# Flash_-_S25FL216K0PMFI041.net
KiCad netlist of a schematic drawn in Altium Designer
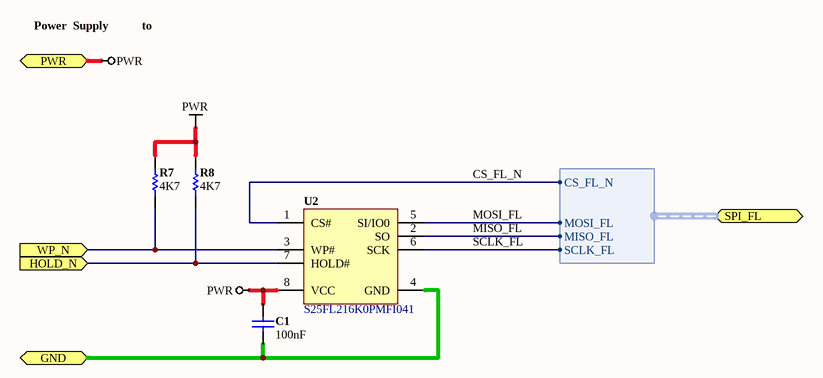
[diagram p0: Flash - S25FL216K0PMFI041.SchDoc]

(export (version "E")
  (design (tool "Eeschema 10.0.6"))
  (components
    (comp (ref "C1")
      (value "100nF")
      (footprint "CAPC0402(1005)60_L")
      (fields
        (field (name "TOLERANCE") "±10%")
        (field (name "MANUFACTURER PART NUMBER") "C0402C104K8PACTU")
        (field (name "Comment") "CAP 100nF 16V 0402(1005)")
      )
      (libsource (lib "Component_Database") (part "CAP_NP"))
    )
    (comp (ref "R7")
      (value "4K7")
      (footprint "RESC0402(1005)40_L")
      (fields
        (field (name "POWER") "1/16 W")
        (field (name "MANUFACTURER PART NUMBER") "CR0402-FX-4701GLFDKR-ND")
      )
      (libsource (lib "Component_Database") (part "RES"))
    )
    (comp (ref "R8")
      (value "4K7")
      (footprint "RESC0402(1005)40_L")
      (fields
        (field (name "POWER") "1/16 W")
        (field (name "MANUFACTURER PART NUMBER") "CR0402-FX-4701GLFDKR-ND")
      )
      (libsource (lib "Component_Database") (part "RES"))
    )
    (comp (ref "U2")
      (value "S25FL216K0PMFI041")
      (footprint "SPANSION-SOIC127P600X175-8M")
      (description "16-Mbit 3.0V Serial Flash Memory with Uniform 4 kB Sectors")
      (libsource (lib "S25FL216K0PMFI041") (part "S25FL216K0PMFI041"))
    )
  )
  (nets
    (net (code "2") (name "/CS_FL_N") (class "Default")
      (node (ref "U2") (pin "1") (pinfunction "CS#_1") (pintype "passive"))
    )
    (net (code "3") (name "/GND") (class "Default")
      (node (ref "C1") (pin "2") (pinfunction "2_2") (pintype "passive"))
      (node (ref "U2") (pin "4") (pinfunction "GND_4") (pintype "passive"))
    )
    (net (code "4") (name "/HOLD_N") (class "Default")
      (node (ref "R8") (pin "1") (pinfunction "1_1") (pintype "passive"))
      (node (ref "U2") (pin "7") (pinfunction "HOLD#_7") (pintype "passive"))
    )
    (net (code "5") (name "/MISO_FL") (class "Default")
      (node (ref "U2") (pin "2") (pinfunction "SO_2") (pintype "passive"))
    )
    (net (code "6") (name "/MOSI_FL") (class "Default")
      (node (ref "U2") (pin "5") (pinfunction "SI/IO0_5") (pintype "passive"))
    )
    (net (code "7") (name "/SCLK_FL") (class "Default")
      (node (ref "U2") (pin "6") (pinfunction "SCK_6") (pintype "passive"))
    )
    (net (code "8") (name "/WP_N") (class "Default")
      (node (ref "R7") (pin "1") (pinfunction "1_1") (pintype "passive"))
      (node (ref "U2") (pin "3") (pinfunction "WP#_3") (pintype "passive"))
    )
    (net (code "10") (name "PWR") (class "Default")
      (node (ref "C1") (pin "1") (pinfunction "1_1") (pintype "passive"))
      (node (ref "R7") (pin "2") (pinfunction "2_2") (pintype "passive"))
      (node (ref "R8") (pin "2") (pinfunction "2_2") (pintype "passive"))
      (node (ref "U2") (pin "8") (pinfunction "VCC_8") (pintype "passive"))
    )
  )
)
